# pca20017_motors.net
KiCad netlist of a schematic drawn in Altium Designer
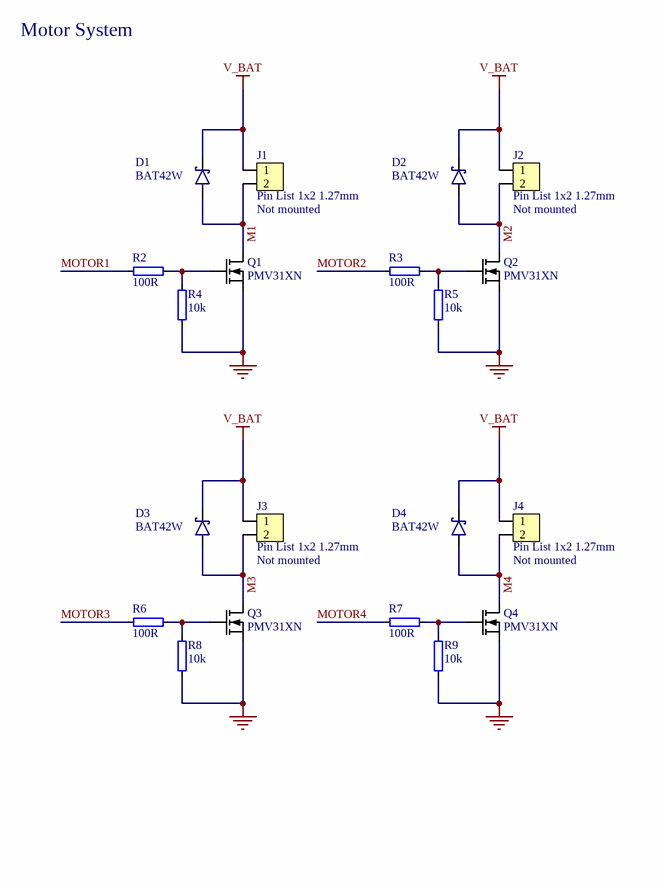
[diagram p0: pca20017_motors.SchDoc]

(export (version "E")
  (design (tool "Eeschema 10.0.6"))
  (components
    (comp (ref "D1")
      (value "BAT42W")
      (footprint "SOD-123")
      (description "Diode Schottky, Vr=30V, If=200mA, Vf=400mV, SOD-123")
      (fields (field (name "MANUFACTURER") "Multicomp") (field (name "PUBLISHER") "Nordic Semiconductor"))
      (libsource (lib "Nordic Discrete DB") (part "D{colon}SCHOTTKY"))
    )
    (comp (ref "D2")
      (value "BAT42W")
      (footprint "SOD-123")
      (description "Diode Schottky, Vr=30V, If=200mA, Vf=400mV, SOD-123")
      (fields (field (name "MANUFACTURER") "Multicomp") (field (name "PUBLISHER") "Nordic Semiconductor"))
      (libsource (lib "Nordic Discrete DB") (part "D{colon}SCHOTTKY"))
    )
    (comp (ref "D3")
      (value "BAT42W")
      (footprint "SOD-123")
      (description "Diode Schottky, Vr=30V, If=200mA, Vf=400mV, SOD-123")
      (fields (field (name "MANUFACTURER") "Multicomp") (field (name "PUBLISHER") "Nordic Semiconductor"))
      (libsource (lib "Nordic Discrete DB") (part "D{colon}SCHOTTKY"))
    )
    (comp (ref "D4")
      (value "BAT42W")
      (footprint "SOD-123")
      (description "Diode Schottky, Vr=30V, If=200mA, Vf=400mV, SOD-123")
      (fields (field (name "MANUFACTURER") "Multicomp") (field (name "PUBLISHER") "Nordic Semiconductor"))
      (libsource (lib "Nordic Discrete DB") (part "D{colon}SCHOTTKY"))
    )
    (comp (ref "J1")
      (value "Pin List 1x2 1.27mm")
      (footprint "LIST_1x2_TH_1.27mm_N.C.")
      (description "Pin List 1x2, 1.27mm (50mil), N.C.")
      (fields
        (field (name "PART NUMBER") "Pin List 1x2 TH, 1.27mm, N.C.")
        (field (name "ASSEMBLY") "Not mounted")
        (field (name "PUBLISHER") "Nordic Semiconductor")
      )
      (libsource (lib "Nordic Passive DB") (part "CONN-2"))
    )
    (comp (ref "J2")
      (value "Pin List 1x2 1.27mm")
      (footprint "LIST_1x2_TH_1.27mm_N.C.")
      (description "Pin List 1x2, 1.27mm (50mil), N.C.")
      (fields
        (field (name "PART NUMBER") "Pin List 1x2 TH, 1.27mm, N.C.")
        (field (name "ASSEMBLY") "Not mounted")
        (field (name "PUBLISHER") "Nordic Semiconductor")
      )
      (libsource (lib "Nordic Passive DB") (part "CONN-2"))
    )
    (comp (ref "J3")
      (value "Pin List 1x2 1.27mm")
      (footprint "LIST_1x2_TH_1.27mm_N.C.")
      (description "Pin List 1x2, 1.27mm (50mil), N.C.")
      (fields
        (field (name "PART NUMBER") "Pin List 1x2 TH, 1.27mm, N.C.")
        (field (name "ASSEMBLY") "Not mounted")
        (field (name "PUBLISHER") "Nordic Semiconductor")
      )
      (libsource (lib "Nordic Passive DB") (part "CONN-2"))
    )
    (comp (ref "J4")
      (value "Pin List 1x2 1.27mm")
      (footprint "LIST_1x2_TH_1.27mm_N.C.")
      (description "Pin List 1x2, 1.27mm (50mil), N.C.")
      (fields
        (field (name "PART NUMBER") "Pin List 1x2 TH, 1.27mm, N.C.")
        (field (name "ASSEMBLY") "Not mounted")
        (field (name "PUBLISHER") "Nordic Semiconductor")
      )
      (libsource (lib "Nordic Passive DB") (part "CONN-2"))
    )
    (comp (ref "Q1")
      (value "PMV31XN")
      (footprint "SOT-23a")
      (description "N-channel TrenchMOS FET")
      (fields
        (field (name "MANUFACTURER") "NXP")
        (field (name "2ND SOURCE PART NUMBER") "1081481RL")
        (field (name "PUBLISHER") "Nordic Semiconductor")
      )
      (libsource (lib "Nordic Discrete DB") (part "PMV31XN"))
    )
    (comp (ref "Q2")
      (value "PMV31XN")
      (footprint "SOT-23a")
      (description "N-channel TrenchMOS FET")
      (fields
        (field (name "MANUFACTURER") "NXP")
        (field (name "2ND SOURCE PART NUMBER") "1081481RL")
        (field (name "PUBLISHER") "Nordic Semiconductor")
      )
      (libsource (lib "Nordic Discrete DB") (part "PMV31XN"))
    )
    (comp (ref "Q3")
      (value "PMV31XN")
      (footprint "SOT-23a")
      (description "N-channel TrenchMOS FET")
      (fields
        (field (name "MANUFACTURER") "NXP")
        (field (name "2ND SOURCE PART NUMBER") "1081481RL")
        (field (name "PUBLISHER") "Nordic Semiconductor")
      )
      (libsource (lib "Nordic Discrete DB") (part "PMV31XN"))
    )
    (comp (ref "Q4")
      (value "PMV31XN")
      (footprint "SOT-23a")
      (description "N-channel TrenchMOS FET")
      (fields
        (field (name "MANUFACTURER") "NXP")
        (field (name "2ND SOURCE PART NUMBER") "1081481RL")
        (field (name "PUBLISHER") "Nordic Semiconductor")
      )
      (libsource (lib "Nordic Discrete DB") (part "PMV31XN"))
    )
    (comp (ref "R2")
      (value "100R")
      (footprint "RESC1005X04L")
      (description "Resistor, ±1%, 0.063W")
      (fields (field (name "PART NUMBER") "R0402-100") (field (name "PUBLISHER") "Nordic Semiconductor"))
      (libsource (lib "Nordic Passive DB") (part "RES_1"))
    )
    (comp (ref "R3")
      (value "100R")
      (footprint "RESC1005X04L")
      (description "Resistor, ±1%, 0.063W")
      (fields (field (name "PART NUMBER") "R0402-100") (field (name "PUBLISHER") "Nordic Semiconductor"))
      (libsource (lib "Nordic Passive DB") (part "RES_1"))
    )
    (comp (ref "R4")
      (value "10k")
      (footprint "RESC1005X04L")
      (description "Resistor, ±1%, 0.063W")
      (fields (field (name "PART NUMBER") "R0402-10k") (field (name "PUBLISHER") "Nordic Semiconductor"))
      (libsource (lib "Nordic Passive DB") (part "RES_1"))
    )
    (comp (ref "R5")
      (value "10k")
      (footprint "RESC1005X04L")
      (description "Resistor, ±1%, 0.063W")
      (fields (field (name "PART NUMBER") "R0402-10k") (field (name "PUBLISHER") "Nordic Semiconductor"))
      (libsource (lib "Nordic Passive DB") (part "RES_1"))
    )
    (comp (ref "R6")
      (value "100R")
      (footprint "RESC1005X04L")
      (description "Resistor, ±1%, 0.063W")
      (fields (field (name "PART NUMBER") "R0402-100") (field (name "PUBLISHER") "Nordic Semiconductor"))
      (libsource (lib "Nordic Passive DB") (part "RES_1"))
    )
    (comp (ref "R7")
      (value "100R")
      (footprint "RESC1005X04L")
      (description "Resistor, ±1%, 0.063W")
      (fields (field (name "PART NUMBER") "R0402-100") (field (name "PUBLISHER") "Nordic Semiconductor"))
      (libsource (lib "Nordic Passive DB") (part "RES_1"))
    )
    (comp (ref "R8")
      (value "10k")
      (footprint "RESC1005X04L")
      (description "Resistor, ±1%, 0.063W")
      (fields (field (name "PART NUMBER") "R0402-10k") (field (name "PUBLISHER") "Nordic Semiconductor"))
      (libsource (lib "Nordic Passive DB") (part "RES_1"))
    )
    (comp (ref "R9")
      (value "10k")
      (footprint "RESC1005X04L")
      (description "Resistor, ±1%, 0.063W")
      (fields (field (name "PART NUMBER") "R0402-10k") (field (name "PUBLISHER") "Nordic Semiconductor"))
      (libsource (lib "Nordic Passive DB") (part "RES_1"))
    )
  )
  (nets
    (net (code "1") (name "/M1") (class "Default")
      (node (ref "D1") (pin "1") (pinfunction "A_1") (pintype "passive"))
      (node (ref "J1") (pin "2") (pinfunction "2_2") (pintype "passive"))
      (node (ref "Q1") (pin "3") (pinfunction "D_3") (pintype "passive"))
    )
    (net (code "2") (name "/M2") (class "Default")
      (node (ref "D2") (pin "1") (pinfunction "A_1") (pintype "passive"))
      (node (ref "J2") (pin "2") (pinfunction "2_2") (pintype "passive"))
      (node (ref "Q2") (pin "3") (pinfunction "D_3") (pintype "passive"))
    )
    (net (code "3") (name "/M3") (class "Default")
      (node (ref "D3") (pin "1") (pinfunction "A_1") (pintype "passive"))
      (node (ref "J3") (pin "2") (pinfunction "2_2") (pintype "passive"))
      (node (ref "Q3") (pin "3") (pinfunction "D_3") (pintype "passive"))
    )
    (net (code "4") (name "/M4") (class "Default")
      (node (ref "D4") (pin "1") (pinfunction "A_1") (pintype "passive"))
      (node (ref "J4") (pin "2") (pinfunction "2_2") (pintype "passive"))
      (node (ref "Q4") (pin "3") (pinfunction "D_3") (pintype "passive"))
    )
    (net (code "5") (name "/MOTOR1") (class "Default")
      (node (ref "R2") (pin "1") (pinfunction "1_1") (pintype "passive"))
    )
    (net (code "6") (name "/MOTOR2") (class "Default")
      (node (ref "R3") (pin "1") (pinfunction "1_1") (pintype "passive"))
    )
    (net (code "7") (name "/MOTOR3") (class "Default")
      (node (ref "R6") (pin "1") (pinfunction "1_1") (pintype "passive"))
    )
    (net (code "8") (name "/MOTOR4") (class "Default")
      (node (ref "R7") (pin "1") (pinfunction "1_1") (pintype "passive"))
    )
    (net (code "9") (name "GND") (class "Default")
      (node (ref "Q1") (pin "2") (pinfunction "S_2") (pintype "passive"))
      (node (ref "Q2") (pin "2") (pinfunction "S_2") (pintype "passive"))
      (node (ref "Q3") (pin "2") (pinfunction "S_2") (pintype "passive"))
      (node (ref "Q4") (pin "2") (pinfunction "S_2") (pintype "passive"))
      (node (ref "R4") (pin "1") (pinfunction "1_1") (pintype "passive"))
      (node (ref "R5") (pin "1") (pinfunction "1_1") (pintype "passive"))
      (node (ref "R8") (pin "1") (pinfunction "1_1") (pintype "passive"))
      (node (ref "R9") (pin "1") (pinfunction "1_1") (pintype "passive"))
    )
    (net (code "10") (name "Net-(Q1-G)") (class "Default")
      (node (ref "Q1") (pin "1") (pinfunction "G_1") (pintype "passive"))
      (node (ref "R2") (pin "2") (pinfunction "2_2") (pintype "passive"))
      (node (ref "R4") (pin "2") (pinfunction "2_2") (pintype "passive"))
    )
    (net (code "11") (name "Net-(Q2-G)") (class "Default")
      (node (ref "Q2") (pin "1") (pinfunction "G_1") (pintype "passive"))
      (node (ref "R3") (pin "2") (pinfunction "2_2") (pintype "passive"))
      (node (ref "R5") (pin "2") (pinfunction "2_2") (pintype "passive"))
    )
    (net (code "12") (name "Net-(Q3-G)") (class "Default")
      (node (ref "Q3") (pin "1") (pinfunction "G_1") (pintype "passive"))
      (node (ref "R6") (pin "2") (pinfunction "2_2") (pintype "passive"))
      (node (ref "R8") (pin "2") (pinfunction "2_2") (pintype "passive"))
    )
    (net (code "13") (name "Net-(Q4-G)") (class "Default")
      (node (ref "Q4") (pin "1") (pinfunction "G_1") (pintype "passive"))
      (node (ref "R7") (pin "2") (pinfunction "2_2") (pintype "passive"))
      (node (ref "R9") (pin "2") (pinfunction "2_2") (pintype "passive"))
    )
    (net (code "14") (name "V_BAT") (class "Default")
      (node (ref "D1") (pin "3") (pinfunction "C_3") (pintype "passive"))
      (node (ref "D2") (pin "3") (pinfunction "C_3") (pintype "passive"))
      (node (ref "D3") (pin "3") (pinfunction "C_3") (pintype "passive"))
      (node (ref "D4") (pin "3") (pinfunction "C_3") (pintype "passive"))
      (node (ref "J1") (pin "1") (pinfunction "1_1") (pintype "passive"))
      (node (ref "J2") (pin "1") (pinfunction "1_1") (pintype "passive"))
      (node (ref "J3") (pin "1") (pinfunction "1_1") (pintype "passive"))
      (node (ref "J4") (pin "1") (pinfunction "1_1") (pintype "passive"))
    )
  )
)
